# LVC_rev1.net
KiCad netlist of a schematic drawn in EAGLE
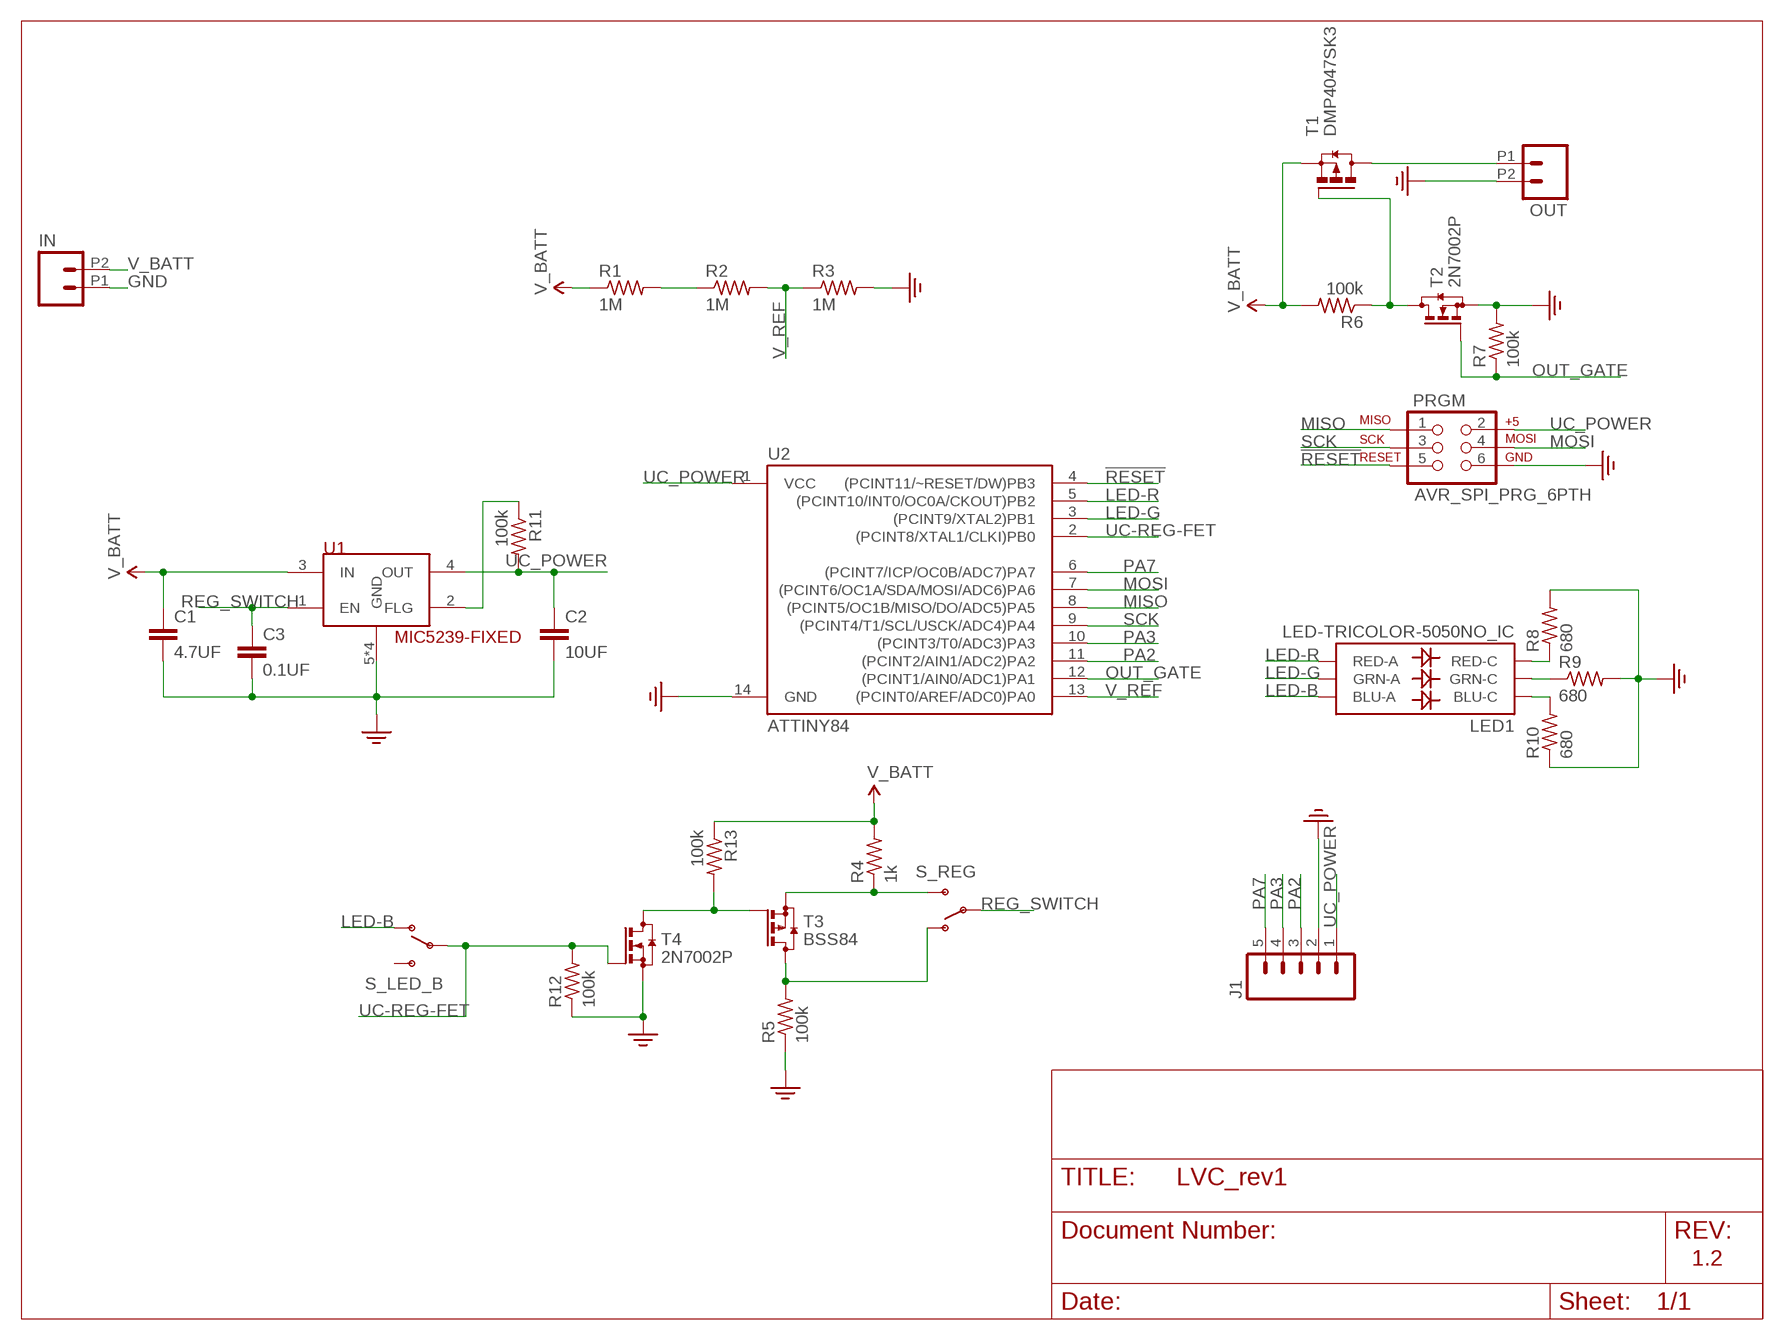
[diagram p0: schematic, sheet 1]

(export (version "E")
  (design (tool "Eeschema 10.0.6"))
  (components
    (comp (ref "C1")
      (value "4.7UF")
      (footprint "eagle-import:C1206")
      (libsource (lib "eagle-import") (part "C-EUC1206"))
    )
    (comp (ref "C2")
      (value "10UF")
      (footprint "eagle-import:C0805")
      (libsource (lib "eagle-import") (part "C-EUC0805"))
    )
    (comp (ref "C3")
      (value "0.1UF")
      (footprint "eagle-import:C0603")
      (libsource (lib "eagle-import") (part "C-EUC0603"))
    )
    (comp (ref "IN")
      (value "M022.54MM_SCREWTERM")
      (footprint "eagle-import:1X02_2.54_SCREWTERM")
      (libsource (lib "eagle-import") (part "M022.54MM_SCREWTERM"))
    )
    (comp (ref "J1")
      (value "M05PTH")
      (footprint "eagle-import:1X05")
      (libsource (lib "eagle-import") (part "M05PTH"))
    )
    (comp (ref "LED1")
      (value "LED-TRICOLOR-5050NO_IC")
      (footprint "eagle-import:LED-TRICOLOR-5050")
      (libsource (lib "eagle-import") (part "LED-TRICOLOR-5050NO_IC"))
    )
    (comp (ref "OUT")
      (value "M022.54MM_SCREWTERM")
      (footprint "eagle-import:1X02_2.54_SCREWTERM")
      (libsource (lib "eagle-import") (part "M022.54MM_SCREWTERM"))
    )
    (comp (ref "PRGM")
      (value "AVR_SPI_PRG_6PTH")
      (footprint "eagle-import:2X3")
      (libsource (lib "eagle-import") (part "AVR_SPI_PRG_6PTH"))
    )
    (comp (ref "R1")
      (value "1M")
      (footprint "eagle-import:R0603")
      (libsource (lib "eagle-import") (part "R-US_R0603"))
    )
    (comp (ref "R2")
      (value "1M")
      (footprint "eagle-import:R0603")
      (libsource (lib "eagle-import") (part "R-US_R0603"))
    )
    (comp (ref "R3")
      (value "1M")
      (footprint "eagle-import:R0603")
      (libsource (lib "eagle-import") (part "R-US_R0603"))
    )
    (comp (ref "R4")
      (value "1k")
      (footprint "eagle-import:R0603")
      (libsource (lib "eagle-import") (part "R-US_R0603"))
    )
    (comp (ref "R5")
      (value "100k")
      (footprint "eagle-import:R0603")
      (libsource (lib "eagle-import") (part "R-US_R0603"))
    )
    (comp (ref "R6")
      (value "100k")
      (footprint "eagle-import:R0603")
      (libsource (lib "eagle-import") (part "R-US_R0603"))
    )
    (comp (ref "R7")
      (value "100k")
      (footprint "eagle-import:R0603")
      (libsource (lib "eagle-import") (part "R-US_R0603"))
    )
    (comp (ref "R8")
      (value "680")
      (footprint "eagle-import:R0603")
      (libsource (lib "eagle-import") (part "R-US_R0603"))
    )
    (comp (ref "R9")
      (value "680")
      (footprint "eagle-import:R0603")
      (libsource (lib "eagle-import") (part "R-US_R0603"))
    )
    (comp (ref "R10")
      (value "680")
      (footprint "eagle-import:R0603")
      (libsource (lib "eagle-import") (part "R-US_R0603"))
    )
    (comp (ref "R11")
      (value "100k")
      (footprint "eagle-import:R0603")
      (libsource (lib "eagle-import") (part "R-US_R0603"))
    )
    (comp (ref "R12")
      (value "100k")
      (footprint "eagle-import:R0603")
      (libsource (lib "eagle-import") (part "R-US_R0603"))
    )
    (comp (ref "R13")
      (value "100k")
      (footprint "eagle-import:R0603")
      (libsource (lib "eagle-import") (part "R-US_R0603"))
    )
    (comp (ref "S_LED_B")
      (value "SWITCH-SPDTPTH")
      (footprint "eagle-import:SWITCH-SPDT")
      (libsource (lib "eagle-import") (part "SWITCH-SPDTPTH"))
    )
    (comp (ref "S_REG")
      (value "SWITCH-SPDTPTH")
      (footprint "eagle-import:SWITCH-SPDT")
      (libsource (lib "eagle-import") (part "SWITCH-SPDTPTH"))
    )
    (comp (ref "T1")
      (value "DMP4047SK3")
      (footprint "eagle-import:TO252")
      (libsource (lib "eagle-import") (part "DMP4047SK3"))
    )
    (comp (ref "T2")
      (value "2N7002P")
      (footprint "eagle-import:SOT23")
      (libsource (lib "eagle-import") (part "2N7002P"))
    )
    (comp (ref "T3")
      (value "BSS84")
      (footprint "eagle-import:SOT23")
      (libsource (lib "eagle-import") (part "BSS84"))
    )
    (comp (ref "T4")
      (value "2N7002P")
      (footprint "eagle-import:SOT23")
      (libsource (lib "eagle-import") (part "2N7002P"))
    )
    (comp (ref "U1")
      (value "MIC5239-FIXED")
      (footprint "eagle-import:SOIC8")
      (libsource (lib "eagle-import") (part "MIC5239-FIXED"))
    )
    (comp (ref "U2")
      (value "ATTINY84")
      (footprint "eagle-import:SO14")
      (libsource (lib "eagle-import") (part "ATTINY84"))
    )
  )
  (nets
    (net (code "1") (name "/LED-B") (class "Default")
      (node (ref "LED1") (pin "3") (pinfunction "BLU-A_3") (pintype "bidirectional"))
      (node (ref "S_LED_B") (pin "1") (pinfunction "O_1") (pintype "passive"))
    )
    (net (code "2") (name "/LED-G") (class "Default")
      (node (ref "LED1") (pin "1") (pinfunction "GRN-A_1") (pintype "bidirectional"))
      (node (ref "U2") (pin "3") (pinfunction "(PCINT9/XTAL2)PB1_3") (pintype "bidirectional"))
    )
    (net (code "3") (name "/LED-R") (class "Default")
      (node (ref "LED1") (pin "2") (pinfunction "RED-A_2") (pintype "bidirectional"))
      (node (ref "U2") (pin "5") (pinfunction "(PCINT10/INT0/OC0A/CKOUT)PB2_5") (pintype "bidirectional"))
    )
    (net (code "4") (name "/MISO") (class "Default")
      (node (ref "PRGM") (pin "1") (pinfunction "1_1") (pintype "passive"))
      (node (ref "U2") (pin "8") (pinfunction "(PCINT5/OC1B/MISO/DO/ADC5)PA5_8") (pintype "bidirectional"))
    )
    (net (code "5") (name "/MOSI") (class "Default")
      (node (ref "PRGM") (pin "4") (pinfunction "4_4") (pintype "passive"))
      (node (ref "U2") (pin "7") (pinfunction "(PCINT6/OC1A/SDA/MOSI/ADC6)PA6_7") (pintype "bidirectional"))
    )
    (net (code "6") (name "/OUT_GATE") (class "Default")
      (node (ref "R7") (pin "1") (pinfunction "1_1") (pintype "passive"))
      (node (ref "T2") (pin "1") (pinfunction "G_1") (pintype "passive"))
      (node (ref "U2") (pin "12") (pinfunction "(PCINT1/AIN0/ADC1)PA1_12") (pintype "bidirectional"))
    )
    (net (code "7") (name "/PA2") (class "Default")
      (node (ref "J1") (pin "3") (pinfunction "3_3") (pintype "passive"))
      (node (ref "U2") (pin "11") (pinfunction "(PCINT2/AIN1/ADC2)PA2_11") (pintype "bidirectional"))
    )
    (net (code "8") (name "/PA3") (class "Default")
      (node (ref "J1") (pin "4") (pinfunction "4_4") (pintype "passive"))
      (node (ref "U2") (pin "10") (pinfunction "(PCINT3/T0/ADC3)PA3_10") (pintype "bidirectional"))
    )
    (net (code "9") (name "/PA7") (class "Default")
      (node (ref "J1") (pin "5") (pinfunction "5_5") (pintype "passive"))
      (node (ref "U2") (pin "6") (pinfunction "(PCINT7/ICP/OC0B/ADC7)PA7_6") (pintype "bidirectional"))
    )
    (net (code "10") (name "/REG_SWITCH") (class "Default")
      (node (ref "C3") (pin "1") (pinfunction "1_1") (pintype "passive"))
      (node (ref "S_REG") (pin "2") (pinfunction "P_2") (pintype "passive"))
      (node (ref "U1") (pin "1") (pinfunction "EN_1") (pintype "input"))
    )
    (net (code "11") (name "/SCK") (class "Default")
      (node (ref "PRGM") (pin "3") (pinfunction "3_3") (pintype "passive"))
      (node (ref "U2") (pin "9") (pinfunction "(PCINT4/T1/SCL/USCK/ADC4)PA4_9") (pintype "bidirectional"))
    )
    (net (code "12") (name "/UC-REG-FET") (class "Default")
      (node (ref "R12") (pin "2") (pinfunction "2_2") (pintype "passive"))
      (node (ref "S_LED_B") (pin "2") (pinfunction "P_2") (pintype "passive"))
      (node (ref "T4") (pin "1") (pinfunction "G_1") (pintype "passive"))
      (node (ref "U2") (pin "2") (pinfunction "(PCINT8/XTAL1/CLKI)PB0_2") (pintype "bidirectional"))
    )
    (net (code "13") (name "/UC_POWER") (class "Default")
      (node (ref "C2") (pin "1") (pinfunction "1_1") (pintype "passive"))
      (node (ref "J1") (pin "1") (pinfunction "1_1") (pintype "passive"))
      (node (ref "PRGM") (pin "2") (pinfunction "2_2") (pintype "passive"))
      (node (ref "R11") (pin "2") (pinfunction "2_2") (pintype "passive"))
      (node (ref "U1") (pin "4") (pinfunction "OUT_4") (pintype "output"))
      (node (ref "U2") (pin "1") (pinfunction "VCC_1") (pintype "bidirectional"))
    )
    (net (code "14") (name "/V_REF") (class "Default")
      (node (ref "R2") (pin "2") (pinfunction "2_2") (pintype "passive"))
      (node (ref "R3") (pin "1") (pinfunction "1_1") (pintype "passive"))
      (node (ref "U2") (pin "13") (pinfunction "(PCINT0/AREF/ADC0)PA0_13") (pintype "bidirectional"))
    )
    (net (code "15") (name "/~{RESET}") (class "Default")
      (node (ref "PRGM") (pin "5") (pinfunction "5_5") (pintype "passive"))
      (node (ref "U2") (pin "4") (pinfunction "(PCINT11/~{RESET/DW})PB3_4") (pintype "bidirectional"))
    )
    (net (code "16") (name "GND-NONAME") (class "Default")
      (node (ref "C1") (pin "2") (pinfunction "2_2") (pintype "passive"))
      (node (ref "C2") (pin "2") (pinfunction "2_2") (pintype "passive"))
      (node (ref "C3") (pin "2") (pinfunction "2_2") (pintype "passive"))
      (node (ref "IN") (pin "P1") (pinfunction "1_P1") (pintype "passive"))
      (node (ref "J1") (pin "2") (pinfunction "2_2") (pintype "passive"))
      (node (ref "OUT") (pin "P2") (pinfunction "2_P2") (pintype "passive"))
      (node (ref "PRGM") (pin "6") (pinfunction "6_6") (pintype "passive"))
      (node (ref "R10") (pin "1") (pinfunction "1_1") (pintype "passive"))
      (node (ref "R12") (pin "1") (pinfunction "1_1") (pintype "passive"))
      (node (ref "R3") (pin "2") (pinfunction "2_2") (pintype "passive"))
      (node (ref "R5") (pin "1") (pinfunction "1_1") (pintype "passive"))
      (node (ref "R7") (pin "2") (pinfunction "2_2") (pintype "passive"))
      (node (ref "R8") (pin "2") (pinfunction "2_2") (pintype "passive"))
      (node (ref "R9") (pin "2") (pinfunction "2_2") (pintype "passive"))
      (node (ref "T2") (pin "2") (pinfunction "S_2") (pintype "passive"))
      (node (ref "T4") (pin "2") (pinfunction "S_2") (pintype "passive"))
      (node (ref "U1") (pin "5") (pinfunction "GND_5") (pintype "power_in"))
      (node (ref "U1") (pin "6") (pinfunction "GND_6") (pintype "power_in"))
      (node (ref "U1") (pin "7") (pinfunction "GND_7") (pintype "power_in"))
      (node (ref "U1") (pin "8") (pinfunction "GND_8") (pintype "power_in"))
      (node (ref "U2") (pin "14") (pinfunction "GND_14") (pintype "bidirectional"))
    )
    (net (code "17") (name "Net-(LED1-BLU-C)") (class "Default")
      (node (ref "LED1") (pin "4") (pinfunction "BLU-C_4") (pintype "bidirectional"))
      (node (ref "R10") (pin "2") (pinfunction "2_2") (pintype "passive"))
    )
    (net (code "18") (name "Net-(LED1-GRN-C)") (class "Default")
      (node (ref "LED1") (pin "6") (pinfunction "GRN-C_6") (pintype "bidirectional"))
      (node (ref "R9") (pin "1") (pinfunction "1_1") (pintype "passive"))
    )
    (net (code "19") (name "Net-(LED1-RED-C)") (class "Default")
      (node (ref "LED1") (pin "5") (pinfunction "RED-C_5") (pintype "bidirectional"))
      (node (ref "R8") (pin "1") (pinfunction "1_1") (pintype "passive"))
    )
    (net (code "20") (name "Net-(OUT-1)") (class "Default")
      (node (ref "OUT") (pin "P1") (pinfunction "1_P1") (pintype "passive"))
      (node (ref "T1") (pin "3") (pinfunction "D_3") (pintype "passive"))
    )
    (net (code "21") (name "Net-(R1-Pad2)") (class "Default")
      (node (ref "R1") (pin "2") (pinfunction "2_2") (pintype "passive"))
      (node (ref "R2") (pin "1") (pinfunction "1_1") (pintype "passive"))
    )
    (net (code "22") (name "Net-(S_REG-O)") (class "Default")
      (node (ref "R5") (pin "2") (pinfunction "2_2") (pintype "passive"))
      (node (ref "S_REG") (pin "1") (pinfunction "O_1") (pintype "passive"))
      (node (ref "T3") (pin "3") (pinfunction "D_3") (pintype "passive"))
    )
    (net (code "23") (name "Net-(S_REG-S)") (class "Default")
      (node (ref "R4") (pin "1") (pinfunction "1_1") (pintype "passive"))
      (node (ref "S_REG") (pin "3") (pinfunction "S_3") (pintype "passive"))
      (node (ref "T3") (pin "2") (pinfunction "S_2") (pintype "passive"))
    )
    (net (code "24") (name "Net-(T1-G)") (class "Default")
      (node (ref "R6") (pin "1") (pinfunction "1_1") (pintype "passive"))
      (node (ref "T1") (pin "1") (pinfunction "G_1") (pintype "passive"))
      (node (ref "T2") (pin "3") (pinfunction "D_3") (pintype "passive"))
    )
    (net (code "25") (name "Net-(T3-G)") (class "Default")
      (node (ref "R13") (pin "2") (pinfunction "2_2") (pintype "passive"))
      (node (ref "T3") (pin "1") (pinfunction "G_1") (pintype "passive"))
      (node (ref "T4") (pin "3") (pinfunction "D_3") (pintype "passive"))
    )
    (net (code "26") (name "Net-(U1-FLG)") (class "Default")
      (node (ref "R11") (pin "1") (pinfunction "1_1") (pintype "passive"))
      (node (ref "U1") (pin "2") (pinfunction "FLG_2") (pintype "output"))
    )
    (net (code "27") (name "V_BATT") (class "Default")
      (node (ref "C1") (pin "1") (pinfunction "1_1") (pintype "passive"))
      (node (ref "IN") (pin "P2") (pinfunction "2_P2") (pintype "passive"))
      (node (ref "R1") (pin "1") (pinfunction "1_1") (pintype "passive"))
      (node (ref "R13") (pin "1") (pinfunction "1_1") (pintype "passive"))
      (node (ref "R4") (pin "2") (pinfunction "2_2") (pintype "passive"))
      (node (ref "R6") (pin "2") (pinfunction "2_2") (pintype "passive"))
      (node (ref "T1") (pin "2") (pinfunction "S_2") (pintype "passive"))
      (node (ref "U1") (pin "3") (pinfunction "IN_3") (pintype "power_in"))
    )
    (net (code "28") (name "unconnected-(S_LED_B-S-Pad3)") (class "Default")
      (node (ref "S_LED_B") (pin "3") (pinfunction "S_3") (pintype "passive"))
    )
  )
)
